# programmer9_0.net
KiCad netlist of a schematic drawn in EAGLE
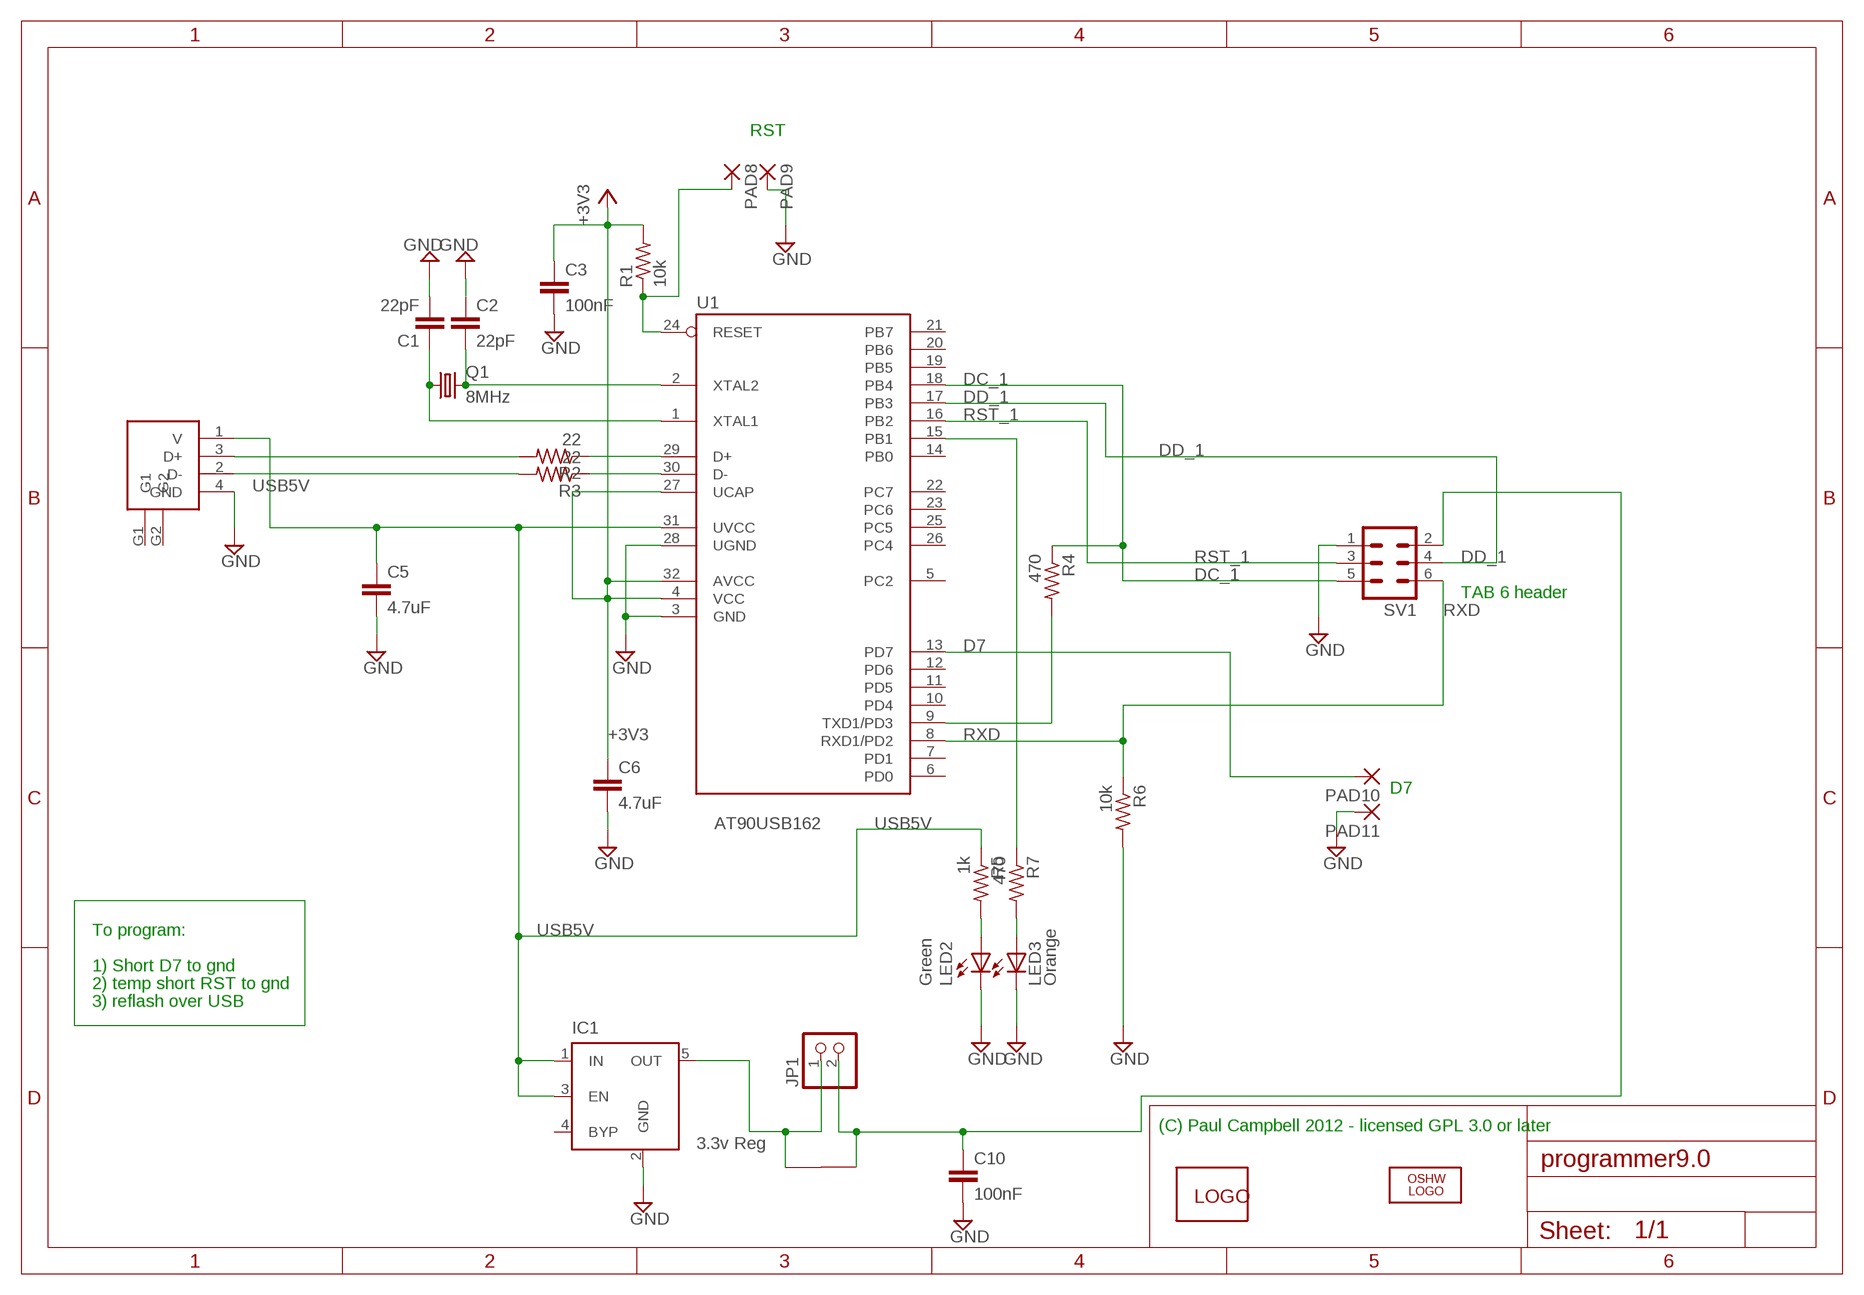
[diagram p0: schematic, sheet 1]

(export (version "E")
  (design (tool "Eeschema 10.0.6"))
  (components
    (comp (ref "C1")
      (value "22pF")
      (footprint "eagle-import:C0603")
      (libsource (lib "eagle-import") (part "C-EUC0603"))
    )
    (comp (ref "C2")
      (value "22pF")
      (footprint "eagle-import:C0603")
      (libsource (lib "eagle-import") (part "C-EUC0603"))
    )
    (comp (ref "C3")
      (value "100nF")
      (footprint "eagle-import:C0603")
      (libsource (lib "eagle-import") (part "C-EUC0603"))
    )
    (comp (ref "C5")
      (value "4.7uF")
      (footprint "eagle-import:C0805")
      (libsource (lib "eagle-import") (part "C-EUC0805"))
    )
    (comp (ref "C6")
      (value "4.7uF")
      (footprint "eagle-import:C0805")
      (libsource (lib "eagle-import") (part "C-EUC0805"))
    )
    (comp (ref "C10")
      (value "100nF")
      (footprint "eagle-import:C0603")
      (libsource (lib "eagle-import") (part "C-EUC0603"))
    )
    (comp (ref "IC1")
      (value "3.3v Reg")
      (footprint "eagle-import:SOT23-5")
      (libsource (lib "eagle-import") (part "MIC5219XX"))
    )
    (comp (ref "JP1")
      (value "PINHD-1X2")
      (footprint "eagle-import:1X02")
      (libsource (lib "eagle-import") (part "PINHD-1X2"))
    )
    (comp (ref "LED2")
      (value "Green")
      (footprint "eagle-import:CHIP-LED0805")
      (libsource (lib "eagle-import") (part "LEDCHIP-LED0805"))
    )
    (comp (ref "LED3")
      (value "Orange")
      (footprint "eagle-import:CHIP-LED0805")
      (libsource (lib "eagle-import") (part "LEDCHIP-LED0805"))
    )
    (comp (ref "LOGO2")
      (value "OSHW_LOGO_FILLX0100-NT")
      (footprint "eagle-import:OSHW_FILLX100_NOTEXT")
      (libsource (lib "eagle-import") (part "OSHW_LOGO_FILLX0100-NT"))
    )
    (comp (ref "PAD8")
      (value "1,6/0,8")
      (footprint "eagle-import:1,6_0,8")
      (libsource (lib "eagle-import") (part "1,6/0,8"))
    )
    (comp (ref "PAD9")
      (value "1,6/0,8")
      (footprint "eagle-import:1,6_0,8")
      (libsource (lib "eagle-import") (part "1,6/0,8"))
    )
    (comp (ref "PAD10")
      (value "1,6/0,8")
      (footprint "eagle-import:1,6_0,8")
      (libsource (lib "eagle-import") (part "1,6/0,8"))
    )
    (comp (ref "PAD11")
      (value "1,6/0,8")
      (footprint "eagle-import:1,6_0,8")
      (libsource (lib "eagle-import") (part "1,6/0,8"))
    )
    (comp (ref "Q1")
      (value "8MHz")
      (footprint "eagle-import:HC49UP")
      (libsource (lib "eagle-import") (part "CRYSTALHC49UP"))
    )
    (comp (ref "R1")
      (value "10k")
      (footprint "eagle-import:R0603")
      (libsource (lib "eagle-import") (part "R-US_R0603"))
    )
    (comp (ref "R2")
      (value "22")
      (footprint "eagle-import:R0603")
      (libsource (lib "eagle-import") (part "R-US_R0603"))
    )
    (comp (ref "R3")
      (value "22")
      (footprint "eagle-import:R0603")
      (libsource (lib "eagle-import") (part "R-US_R0603"))
    )
    (comp (ref "R4")
      (value "470")
      (footprint "eagle-import:R0603")
      (libsource (lib "eagle-import") (part "R-US_R0603"))
    )
    (comp (ref "R5")
      (value "1k")
      (footprint "eagle-import:R0603")
      (libsource (lib "eagle-import") (part "R-US_R0603"))
    )
    (comp (ref "R6")
      (value "10k")
      (footprint "eagle-import:R0603")
      (libsource (lib "eagle-import") (part "R-US_R0603"))
    )
    (comp (ref "R7")
      (value "470")
      (footprint "eagle-import:R0603")
      (libsource (lib "eagle-import") (part "R-US_R0603"))
    )
    (comp (ref "SV1")
      (value "MA03-2")
      (footprint "eagle-import:MA03-2")
      (libsource (lib "eagle-import") (part "MA03-2"))
    )
    (comp (ref "U$1")
      (value "LINK")
      (footprint "eagle-import:LINK")
      (libsource (lib "eagle-import") (part "LINK"))
    )
    (comp (ref "U$2")
      (value "MOONBASE-LOGO")
      (footprint "eagle-import:MOONBASE-LOGO")
      (libsource (lib "eagle-import") (part "MOONBASE-LOGO"))
    )
    (comp (ref "U$3")
      (value "USB-RAW")
      (footprint "eagle-import:USBY")
      (libsource (lib "eagle-import") (part "USB-RAW"))
    )
    (comp (ref "U1")
      (value "AT90USB162")
      (footprint "eagle-import:TQFP32-08")
      (libsource (lib "eagle-import") (part "AT90USB162"))
    )
  )
  (nets
    (net (code "1") (name "+3V3") (class "Default")
      (node (ref "C3") (pin "1") (pinfunction "1_1") (pintype "passive"))
      (node (ref "C6") (pin "1") (pinfunction "1_1") (pintype "passive"))
      (node (ref "R1") (pin "2") (pinfunction "2_2") (pintype "passive"))
      (node (ref "U1") (pin "27") (pinfunction "UCAP_27") (pintype "bidirectional"))
      (node (ref "U1") (pin "32") (pinfunction "AVCC_32") (pintype "bidirectional"))
      (node (ref "U1") (pin "4") (pinfunction "VCC_4") (pintype "bidirectional"))
    )
    (net (code "2") (name "/D7") (class "Default")
      (node (ref "PAD10") (pin "1") (pinfunction "P_1") (pintype "passive"))
      (node (ref "U1") (pin "13") (pinfunction "PD7_13") (pintype "bidirectional"))
    )
    (net (code "3") (name "/DC_1") (class "Default")
      (node (ref "R4") (pin "1") (pinfunction "1_1") (pintype "passive"))
      (node (ref "SV1") (pin "5") (pinfunction "5_5") (pintype "passive"))
      (node (ref "U1") (pin "18") (pinfunction "PB4_18") (pintype "bidirectional"))
    )
    (net (code "4") (name "/DD_1") (class "Default")
      (node (ref "SV1") (pin "4") (pinfunction "4_4") (pintype "passive"))
      (node (ref "U1") (pin "17") (pinfunction "PB3_17") (pintype "bidirectional"))
    )
    (net (code "5") (name "/RST_1") (class "Default")
      (node (ref "SV1") (pin "3") (pinfunction "3_3") (pintype "passive"))
      (node (ref "U1") (pin "16") (pinfunction "PB2_16") (pintype "bidirectional"))
    )
    (net (code "6") (name "/RXD") (class "Default")
      (node (ref "R6") (pin "1") (pinfunction "1_1") (pintype "passive"))
      (node (ref "SV1") (pin "6") (pinfunction "6_6") (pintype "passive"))
      (node (ref "U1") (pin "8") (pinfunction "RXD1/PD2_8") (pintype "bidirectional"))
    )
    (net (code "7") (name "/USB5V") (class "Default")
      (node (ref "C5") (pin "1") (pinfunction "1_1") (pintype "passive"))
      (node (ref "IC1") (pin "1") (pinfunction "IN_1") (pintype "input"))
      (node (ref "IC1") (pin "3") (pinfunction "EN_3") (pintype "input"))
      (node (ref "R5") (pin "1") (pinfunction "1_1") (pintype "passive"))
      (node (ref "U$3") (pin "1") (pinfunction "V_1") (pintype "bidirectional"))
      (node (ref "U1") (pin "31") (pinfunction "UVCC_31") (pintype "power_in"))
    )
    (net (code "8") (name "GND") (class "Default")
      (node (ref "C1") (pin "2") (pinfunction "2_2") (pintype "passive"))
      (node (ref "C10") (pin "2") (pinfunction "2_2") (pintype "passive"))
      (node (ref "C2") (pin "1") (pinfunction "1_1") (pintype "passive"))
      (node (ref "C3") (pin "2") (pinfunction "2_2") (pintype "passive"))
      (node (ref "C5") (pin "2") (pinfunction "2_2") (pintype "passive"))
      (node (ref "C6") (pin "2") (pinfunction "2_2") (pintype "passive"))
      (node (ref "IC1") (pin "2") (pinfunction "GND_2") (pintype "power_in"))
      (node (ref "LED2") (pin "C") (pinfunction "C_C") (pintype "passive"))
      (node (ref "LED3") (pin "C") (pinfunction "C_C") (pintype "passive"))
      (node (ref "PAD11") (pin "1") (pinfunction "P_1") (pintype "passive"))
      (node (ref "PAD9") (pin "1") (pinfunction "P_1") (pintype "passive"))
      (node (ref "R6") (pin "2") (pinfunction "2_2") (pintype "passive"))
      (node (ref "SV1") (pin "1") (pinfunction "1_1") (pintype "passive"))
      (node (ref "U$3") (pin "4") (pinfunction "GND_4") (pintype "bidirectional"))
      (node (ref "U1") (pin "28") (pinfunction "UGND_28") (pintype "power_in"))
      (node (ref "U1") (pin "3") (pinfunction "GND_3") (pintype "bidirectional"))
    )
    (net (code "9") (name "Net-(IC1-OUT)") (class "Default")
      (node (ref "IC1") (pin "5") (pinfunction "OUT_5") (pintype "output"))
      (node (ref "JP1") (pin "1") (pinfunction "1_1") (pintype "passive"))
      (node (ref "U$1") (pin "1") (pinfunction "P$1_1") (pintype "bidirectional"))
    )
    (net (code "10") (name "Net-(LED2-PadA)") (class "Default")
      (node (ref "LED2") (pin "A") (pinfunction "A_A") (pintype "passive"))
      (node (ref "R5") (pin "2") (pinfunction "2_2") (pintype "passive"))
    )
    (net (code "11") (name "Net-(LED3-PadA)") (class "Default")
      (node (ref "LED3") (pin "A") (pinfunction "A_A") (pintype "passive"))
      (node (ref "R7") (pin "2") (pinfunction "2_2") (pintype "passive"))
    )
    (net (code "12") (name "Net-(PAD8-P)") (class "Default")
      (node (ref "PAD8") (pin "1") (pinfunction "P_1") (pintype "passive"))
      (node (ref "R1") (pin "1") (pinfunction "1_1") (pintype "passive"))
      (node (ref "U1") (pin "24") (pinfunction "RESET_24") (pintype "input"))
    )
    (net (code "13") (name "Net-(U$1-P$2)") (class "Default")
      (node (ref "C10") (pin "1") (pinfunction "1_1") (pintype "passive"))
      (node (ref "JP1") (pin "2") (pinfunction "2_2") (pintype "passive"))
      (node (ref "SV1") (pin "2") (pinfunction "2_2") (pintype "passive"))
      (node (ref "U$1") (pin "2") (pinfunction "P$2_2") (pintype "bidirectional"))
    )
    (net (code "14") (name "Net-(U$3-D+)") (class "Default")
      (node (ref "R2") (pin "2") (pinfunction "2_2") (pintype "passive"))
      (node (ref "U$3") (pin "3") (pinfunction "D+_3") (pintype "bidirectional"))
    )
    (net (code "15") (name "Net-(U$3-D-)") (class "Default")
      (node (ref "R3") (pin "2") (pinfunction "2_2") (pintype "passive"))
      (node (ref "U$3") (pin "2") (pinfunction "D-_2") (pintype "bidirectional"))
    )
    (net (code "16") (name "Net-(U1-D+)") (class "Default")
      (node (ref "R2") (pin "1") (pinfunction "1_1") (pintype "passive"))
      (node (ref "U1") (pin "29") (pinfunction "D+_29") (pintype "bidirectional"))
    )
    (net (code "17") (name "Net-(U1-D-)") (class "Default")
      (node (ref "R3") (pin "1") (pinfunction "1_1") (pintype "passive"))
      (node (ref "U1") (pin "30") (pinfunction "D-_30") (pintype "bidirectional"))
    )
    (net (code "18") (name "Net-(U1-PB1)") (class "Default")
      (node (ref "R7") (pin "1") (pinfunction "1_1") (pintype "passive"))
      (node (ref "U1") (pin "15") (pinfunction "PB1_15") (pintype "bidirectional"))
    )
    (net (code "19") (name "Net-(U1-TXD1{slash}PD3)") (class "Default")
      (node (ref "R4") (pin "2") (pinfunction "2_2") (pintype "passive"))
      (node (ref "U1") (pin "9") (pinfunction "TXD1/PD3_9") (pintype "bidirectional"))
    )
    (net (code "20") (name "Net-(U1-XTAL1)") (class "Default")
      (node (ref "C1") (pin "1") (pinfunction "1_1") (pintype "passive"))
      (node (ref "Q1") (pin "1") (pinfunction "1_1") (pintype "passive"))
      (node (ref "U1") (pin "1") (pinfunction "XTAL1_1") (pintype "bidirectional"))
    )
    (net (code "21") (name "Net-(U1-XTAL2)") (class "Default")
      (node (ref "C2") (pin "2") (pinfunction "2_2") (pintype "passive"))
      (node (ref "Q1") (pin "2") (pinfunction "2_2") (pintype "passive"))
      (node (ref "U1") (pin "2") (pinfunction "XTAL2_2") (pintype "bidirectional"))
    )
    (net (code "22") (name "unconnected-(IC1-BYP-Pad4)") (class "Default")
      (node (ref "IC1") (pin "4") (pinfunction "BYP_4") (pintype "passive"))
    )
    (net (code "23") (name "unconnected-(U$3-PadG1)") (class "Default")
      (node (ref "U$3") (pin "G1") (pinfunction "G1_G1") (pintype "bidirectional"))
    )
    (net (code "24") (name "unconnected-(U$3-PadG2)") (class "Default")
      (node (ref "U$3") (pin "G2") (pinfunction "G2_G2") (pintype "bidirectional"))
    )
    (net (code "25") (name "unconnected-(U1-PB0-Pad14)") (class "Default")
      (node (ref "U1") (pin "14") (pinfunction "PB0_14") (pintype "bidirectional"))
    )
    (net (code "26") (name "unconnected-(U1-PB5-Pad19)") (class "Default")
      (node (ref "U1") (pin "19") (pinfunction "PB5_19") (pintype "bidirectional"))
    )
    (net (code "27") (name "unconnected-(U1-PB6-Pad20)") (class "Default")
      (node (ref "U1") (pin "20") (pinfunction "PB6_20") (pintype "bidirectional"))
    )
    (net (code "28") (name "unconnected-(U1-PB7-Pad21)") (class "Default")
      (node (ref "U1") (pin "21") (pinfunction "PB7_21") (pintype "bidirectional"))
    )
    (net (code "29") (name "unconnected-(U1-PC2-Pad5)") (class "Default")
      (node (ref "U1") (pin "5") (pinfunction "PC2_5") (pintype "bidirectional"))
    )
    (net (code "30") (name "unconnected-(U1-PC4-Pad26)") (class "Default")
      (node (ref "U1") (pin "26") (pinfunction "PC4_26") (pintype "bidirectional"))
    )
    (net (code "31") (name "unconnected-(U1-PC5-Pad25)") (class "Default")
      (node (ref "U1") (pin "25") (pinfunction "PC5_25") (pintype "bidirectional"))
    )
    (net (code "32") (name "unconnected-(U1-PC6-Pad23)") (class "Default")
      (node (ref "U1") (pin "23") (pinfunction "PC6_23") (pintype "bidirectional"))
    )
    (net (code "33") (name "unconnected-(U1-PC7-Pad22)") (class "Default")
      (node (ref "U1") (pin "22") (pinfunction "PC7_22") (pintype "bidirectional"))
    )
    (net (code "34") (name "unconnected-(U1-PD0-Pad6)") (class "Default")
      (node (ref "U1") (pin "6") (pinfunction "PD0_6") (pintype "bidirectional"))
    )
    (net (code "35") (name "unconnected-(U1-PD1-Pad7)") (class "Default")
      (node (ref "U1") (pin "7") (pinfunction "PD1_7") (pintype "bidirectional"))
    )
    (net (code "36") (name "unconnected-(U1-PD4-Pad10)") (class "Default")
      (node (ref "U1") (pin "10") (pinfunction "PD4_10") (pintype "bidirectional"))
    )
    (net (code "37") (name "unconnected-(U1-PD5-Pad11)") (class "Default")
      (node (ref "U1") (pin "11") (pinfunction "PD5_11") (pintype "bidirectional"))
    )
    (net (code "38") (name "unconnected-(U1-PD6-Pad12)") (class "Default")
      (node (ref "U1") (pin "12") (pinfunction "PD6_12") (pintype "bidirectional"))
    )
  )
)
